# Power_Supply.net
KiCad netlist of a schematic drawn in Altium Designer
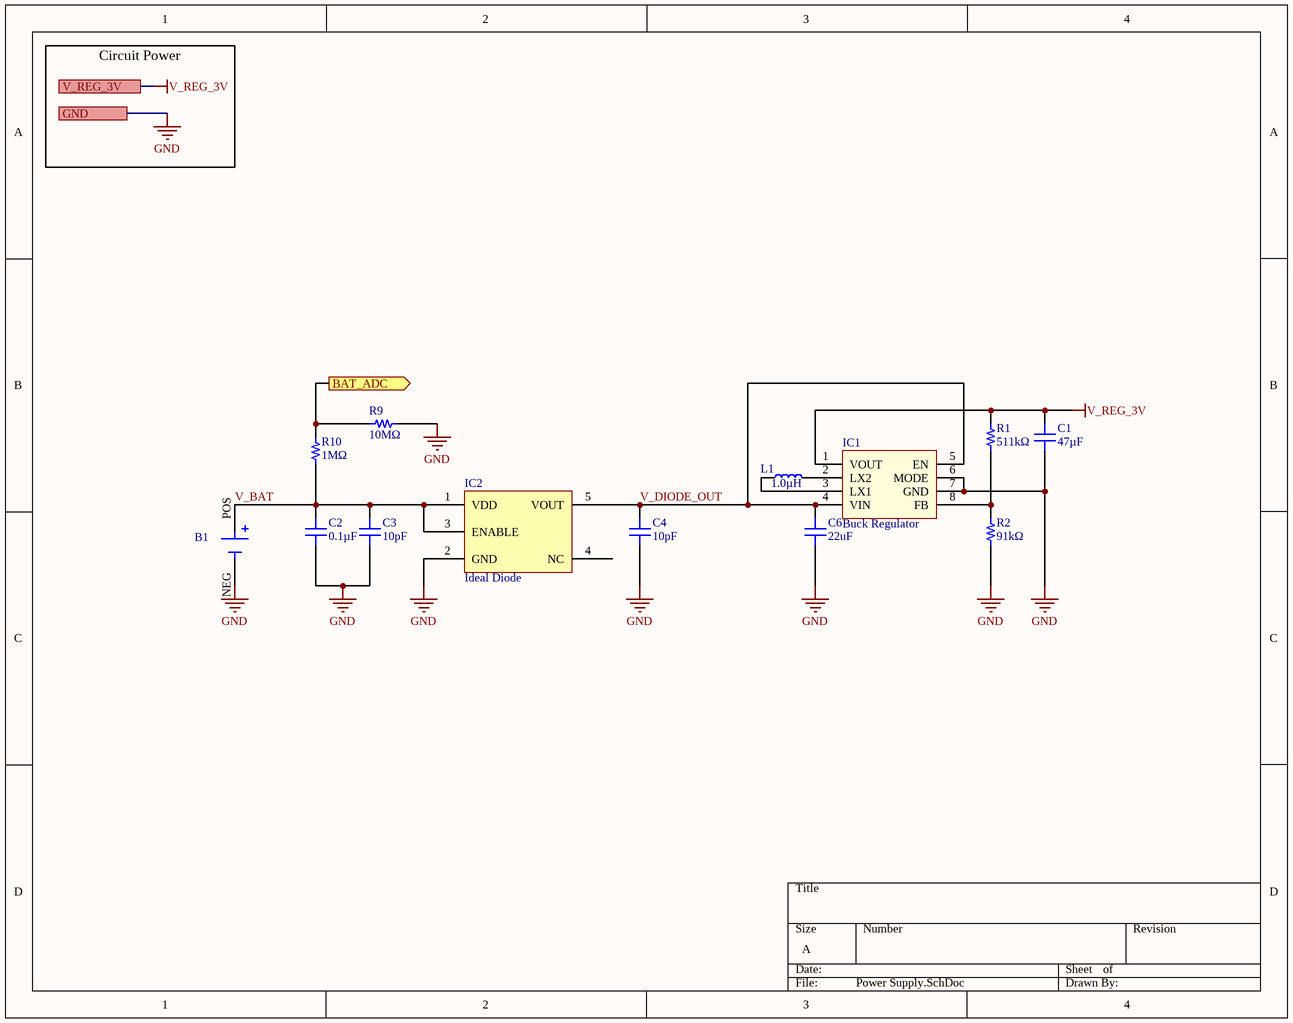
[diagram p0: Power Supply.SchDoc]

(export (version "E")
  (design (tool "Eeschema 10.0.6"))
  (components
    (comp (ref "B1")
      (value "24.5mm Coin Cell (×1)")
      (footprint "MPD BHAA-3")
      (description "BATTERY HOLDER AA PIN")
      (fields (field (name "MANUFACTURER") "MPD (Memory Protection Devices)"))
      (libsource (lib "MVVVMAltiumDatabase") (part "MPD BHAA-3"))
    )
    (comp (ref "C1")
      (value "47µF")
      (footprint "CAP 0805_2012")
      (description "CAP CER 47UF 50V X7R 0805")
      (fields (field (name "MANUFACTURER") "KEMET") (field (name "VOLTAGE") "50V"))
      (libsource (lib "MVVVMAltiumDatabase") (part "Capacitor"))
    )
    (comp (ref "C2")
      (value "0.1µF")
      (footprint "CAP 0402_1005")
      (description "CAP CER 0.1UF 16V X7R 0402")
      (fields (field (name "MANUFACTURER") "KEMET") (field (name "VOLTAGE") "16V"))
      (libsource (lib "MVVVMAltiumDatabase") (part "Capacitor"))
    )
    (comp (ref "C3")
      (value "10pF")
      (footprint "CAP 0603_1608")
      (description "CAP CER 10UF 6.3V X5R 0603")
      (fields (field (name "MANUFACTURER") "KEMET") (field (name "VOLTAGE") "6.3V"))
      (libsource (lib "MVVVMAltiumDatabase") (part "Capacitor"))
    )
    (comp (ref "C4")
      (value "10pF")
      (footprint "CAP 0603_1608")
      (description "CAP CER 10UF 6.3V X5R 0603")
      (fields (field (name "MANUFACTURER") "KEMET") (field (name "VOLTAGE") "6.3V"))
      (libsource (lib "MVVVMAltiumDatabase") (part "Capacitor"))
    )
    (comp (ref "C6")
      (value "22uF")
      (footprint "CAP 0402_1005")
      (description "CAP CER 22UF 50V NPO 0402")
      (fields (field (name "MANUFACTURER") "Walsin") (field (name "VOLTAGE") "50V"))
      (libsource (lib "MVVVMAltiumDatabase") (part "Capacitor"))
    )
    (comp (ref "IC1")
      (value "Buck Regulator")
      (footprint "TI SOT-583")
      (description "DC DC CONVERTER")
      (fields (field (name "MANUFACTURER") "Texas Instruments"))
      (libsource (lib "MVVVMAltiumDatabase") (part "TI TPS631000DRLR"))
    )
    (comp (ref "IC2")
      (value "Ideal Diode")
      (footprint "MAXIM SOT-23-5")
      (description "IC IDEAL DIODE")
      (fields (field (name "MANUFACTURER") "Texas Instruments"))
      (libsource (lib "MVVVMAltiumDatabase") (part "MAXIM MAX40203"))
    )
    (comp (ref "L1")
      (value "1.0µH")
      (footprint "NTC 0603_1608")
      (description "FIXED IND 1.0UH 16V")
      (fields (field (name "MANUFACTURER") "TDK Corporation") (field (name "TOLERANCE") "±20%"))
      (libsource (lib "MVVVMAltiumDatabase") (part "Inductor_2"))
    )
    (comp (ref "R1")
      (value "511kΩ")
      (footprint "RES 0402_1005 RF")
      (description "RES SMD 4.7K OHM 1% 1/8W 0402")
      (fields (field (name "MANUFACTURER") "YAGEO") (field (name "TOLERANCE") "±1%"))
      (libsource (lib "MVVVMAltiumDatabase") (part "Resistor"))
    )
    (comp (ref "R2")
      (value "91kΩ")
      (footprint "RES 0402_1005 RF")
      (description "RES SMD 4.7K OHM 1% 1/8W 0402")
      (fields (field (name "MANUFACTURER") "YAGEO") (field (name "TOLERANCE") "±1%"))
      (libsource (lib "MVVVMAltiumDatabase") (part "Resistor"))
    )
    (comp (ref "R9")
      (value "10MΩ")
      (footprint "RES 0603_1608 RF")
      (description "RES 10M OHM 1% 1/10W 0603")
      (fields (field (name "MANUFACTURER") "Vishay Dale") (field (name "TOLERANCE") "±1%"))
      (libsource (lib "MVVVMAltiumDatabase") (part "Resistor"))
    )
    (comp (ref "R10")
      (value "1MΩ")
      (footprint "RES 0603_1608 RF")
      (description "RES 1M OHM 1% 1/10W 0603")
      (fields (field (name "MANUFACTURER") "Vishay Dale") (field (name "TOLERANCE") "±1%"))
      (libsource (lib "MVVVMAltiumDatabase") (part "Resistor"))
    )
  )
  (nets
    (net (code "1") (name "/BAT_ADC") (class "Default")
      (node (ref "R10") (pin "2") (pinfunction "2_2") (pintype "passive"))
      (node (ref "R9") (pin "1") (pinfunction "1_1") (pintype "passive"))
    )
    (net (code "2") (name "/V_BAT") (class "Default")
      (node (ref "B1") (pin "POS") (pinfunction "POS_POS") (pintype "passive"))
      (node (ref "C2") (pin "2") (pinfunction "2_2") (pintype "passive"))
      (node (ref "C3") (pin "2") (pinfunction "2_2") (pintype "passive"))
      (node (ref "IC2") (pin "1") (pinfunction "VDD_1") (pintype "passive"))
      (node (ref "IC2") (pin "3") (pinfunction "ENABLE_3") (pintype "passive"))
      (node (ref "R10") (pin "1") (pinfunction "1_1") (pintype "passive"))
    )
    (net (code "3") (name "/V_DIODE_OUT") (class "Default")
      (node (ref "C4") (pin "2") (pinfunction "2_2") (pintype "passive"))
      (node (ref "C6") (pin "2") (pinfunction "2_2") (pintype "passive"))
      (node (ref "IC1") (pin "4") (pinfunction "VIN_4") (pintype "passive"))
      (node (ref "IC1") (pin "5") (pinfunction "EN_5") (pintype "passive"))
      (node (ref "IC2") (pin "5") (pinfunction "VOUT_5") (pintype "passive"))
    )
    (net (code "4") (name "GND") (class "Default")
      (node (ref "B1") (pin "NEG") (pinfunction "NEG_NEG") (pintype "passive"))
      (node (ref "C1") (pin "1") (pinfunction "1_1") (pintype "passive"))
      (node (ref "C2") (pin "1") (pinfunction "1_1") (pintype "passive"))
      (node (ref "C3") (pin "1") (pinfunction "1_1") (pintype "passive"))
      (node (ref "C4") (pin "1") (pinfunction "1_1") (pintype "passive"))
      (node (ref "C6") (pin "1") (pinfunction "1_1") (pintype "passive"))
      (node (ref "IC1") (pin "6") (pinfunction "MODE_6") (pintype "passive"))
      (node (ref "IC1") (pin "7") (pinfunction "GND_7") (pintype "passive"))
      (node (ref "IC2") (pin "2") (pinfunction "GND_2") (pintype "passive"))
      (node (ref "R2") (pin "1") (pinfunction "1_1") (pintype "passive"))
      (node (ref "R9") (pin "2") (pinfunction "2_2") (pintype "passive"))
    )
    (net (code "5") (name "Net-(IC1-FB)") (class "Default")
      (node (ref "IC1") (pin "8") (pinfunction "FB_8") (pintype "passive"))
      (node (ref "R1") (pin "1") (pinfunction "1_1") (pintype "passive"))
      (node (ref "R2") (pin "2") (pinfunction "2_2") (pintype "passive"))
    )
    (net (code "6") (name "Net-(IC1-LX1)") (class "Default")
      (node (ref "IC1") (pin "3") (pinfunction "LX1_3") (pintype "passive"))
      (node (ref "L1") (pin "1") (pinfunction "1_1") (pintype "passive"))
    )
    (net (code "7") (name "Net-(IC1-LX2)") (class "Default")
      (node (ref "IC1") (pin "2") (pinfunction "LX2_2") (pintype "passive"))
      (node (ref "L1") (pin "2") (pinfunction "2_2") (pintype "passive"))
    )
    (net (code "8") (name "V_REG_3V") (class "Default")
      (node (ref "C1") (pin "2") (pinfunction "2_2") (pintype "passive"))
      (node (ref "IC1") (pin "1") (pinfunction "VOUT_1") (pintype "passive"))
      (node (ref "R1") (pin "2") (pinfunction "2_2") (pintype "passive"))
    )
    (net (code "9") (name "unconnected-(IC2-NC-Pad4)") (class "Default")
      (node (ref "IC2") (pin "4") (pinfunction "NC_4") (pintype "passive"))
    )
  )
)
